# Mini_inverter_12v_to_220v.net
KiCad netlist of a schematic drawn in EasyEDA Pro
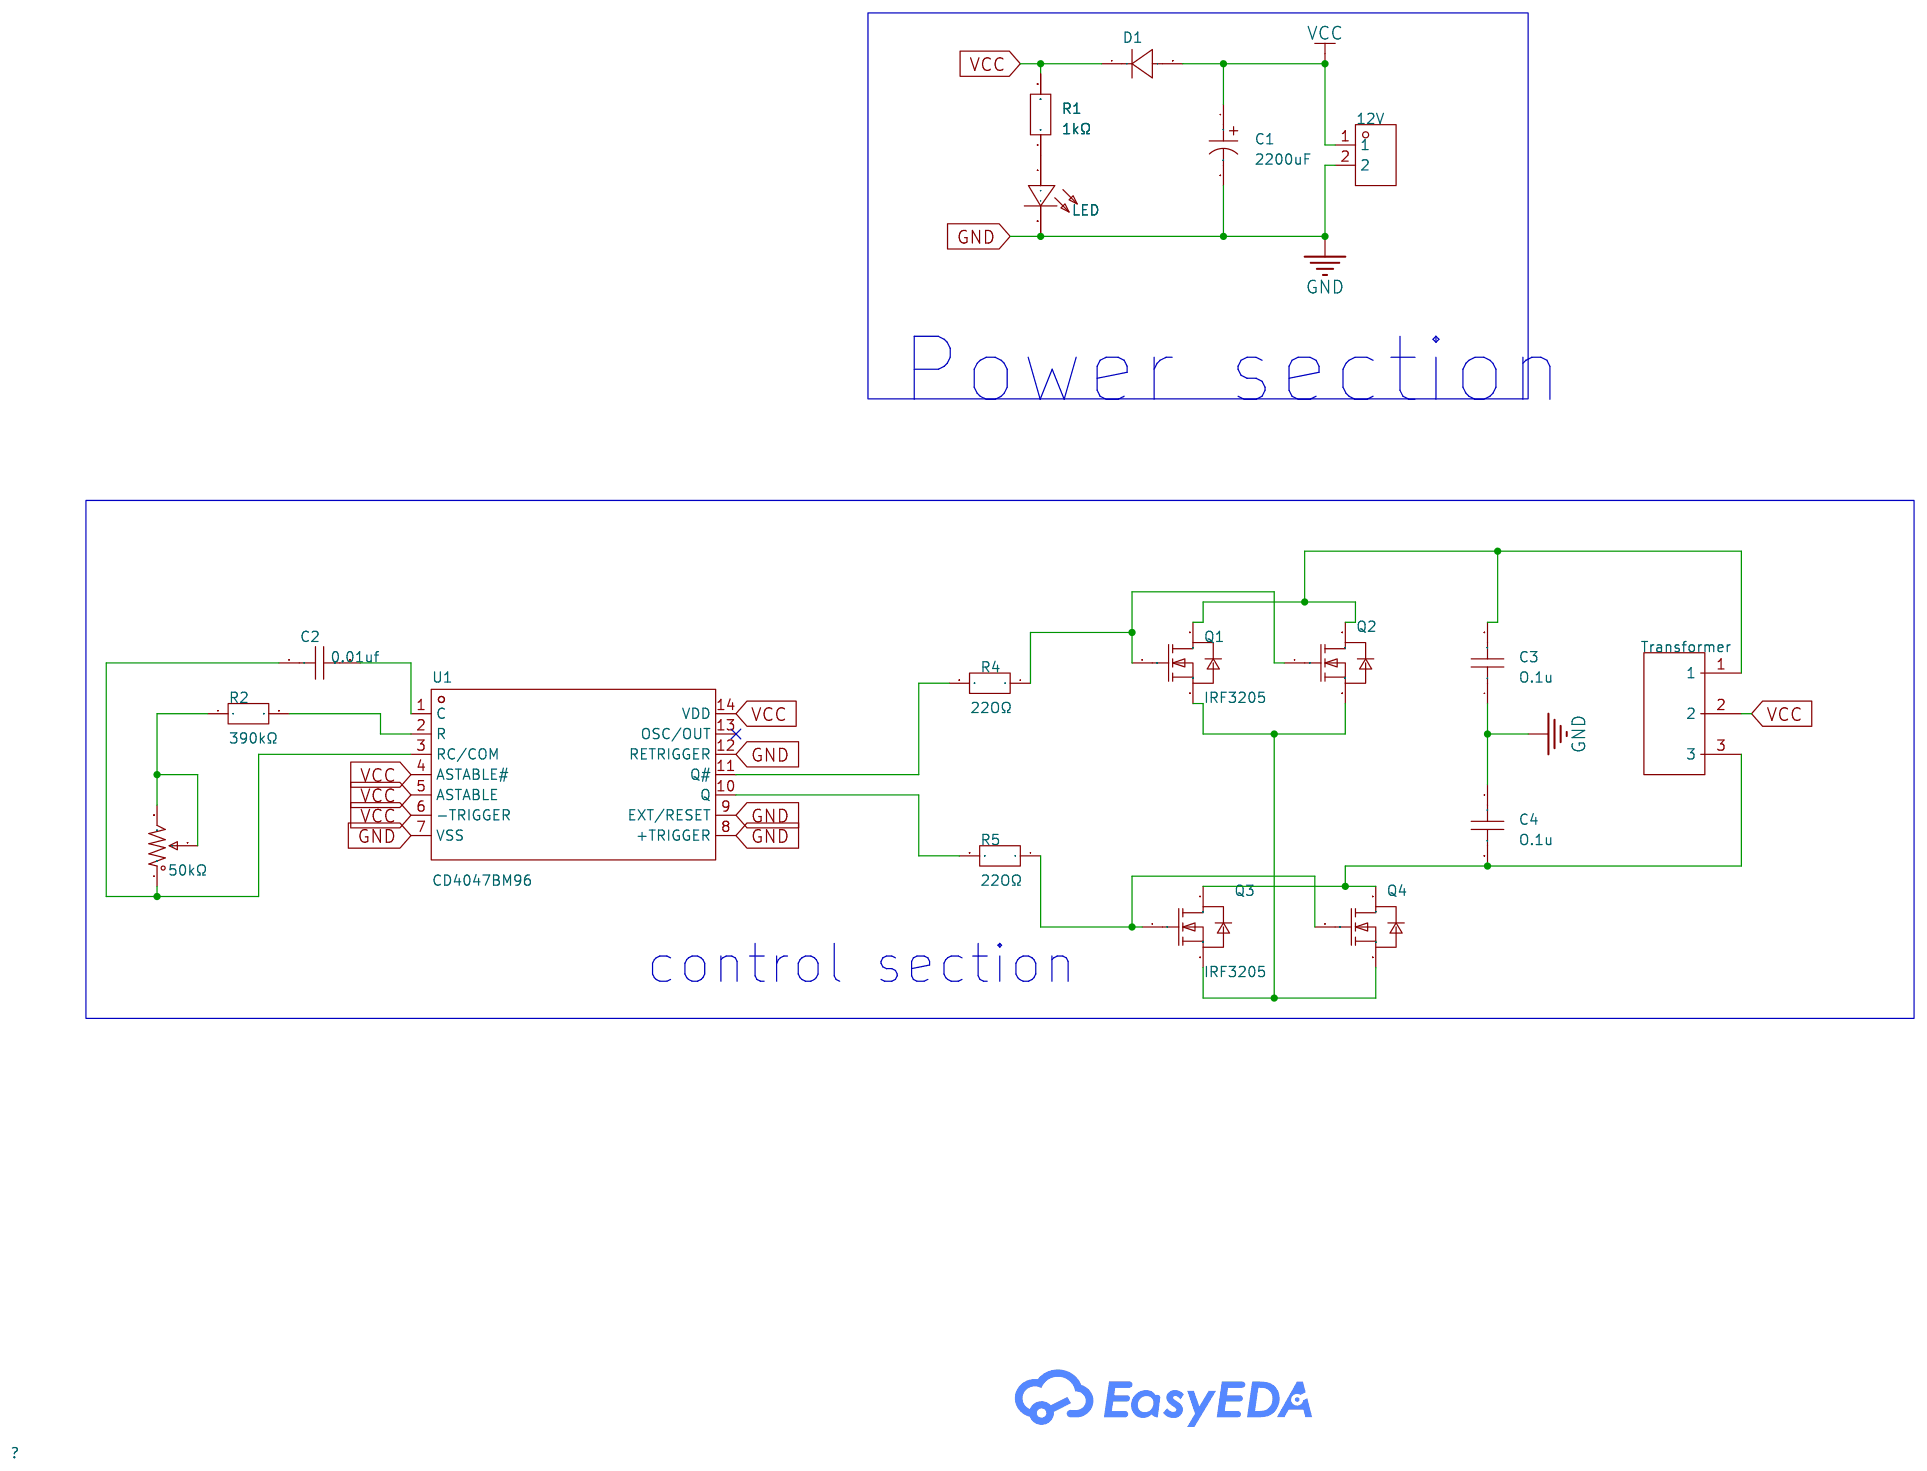
[diagram p0: schematic sheet]

(export (version "E")
  (design (tool "Eeschema 10.0.6"))
  (components
    (comp (ref "12V")
      (value "WJ126V-5.0-2P-16-00A")
      (footprint "easyedapro:CONN-TH_WJ126V-5.0-2P")
      (fields (field (name "Manufacturer") "KANGNEX(康奈克斯电气)"))
      (libsource (lib "easyedapro") (part "WJ126V-5.0-2P-16-00A"))
    )
    (comp (ref "C1")
      (value "2200uF")
      (footprint "easyedapro:CAP-TH_BD13.0-P5.00-D0.6-FD")
      (fields
        (field (name "Manufacturer Part") "ERA25V2200M13X21")
        (field (name "Manufacturer") "JIERR(捷而瑞)")
      )
      (libsource (lib "easyedapro") (part "ERA25V2200M13X21"))
    )
    (comp (ref "C2")
      (value "0.01uf")
      (footprint "easyedapro:C0603")
      (description "Capacitance:10nF Tolerance:±10% Tolerance:±10% Voltage Rating:50V Temperature Coefficient:X7R")
      (fields
        (field (name "Manufacturer Part") "FCC0603B103K500CT")
        (field (name "Manufacturer") "FOJAN(富捷)")
      )
      (libsource (lib "easyedapro") (part "FCC0603B103K500CT"))
    )
    (comp (ref "C3")
      (value "O.1u")
      (footprint "easyedapro:C0603")
      (description "Capacitance:10nF Tolerance:±10% Tolerance:±10% Voltage Rating:50V Temperature Coefficient:X7R")
      (fields
        (field (name "Manufacturer Part") "FCC0603B103K500CT")
        (field (name "Manufacturer") "FOJAN(富捷)")
      )
      (libsource (lib "easyedapro") (part "FCC0603B103K500CT"))
    )
    (comp (ref "C4")
      (value "O.1u")
      (footprint "easyedapro:C0603")
      (description "Capacitance:10nF Tolerance:±10% Tolerance:±10% Voltage Rating:50V Temperature Coefficient:X7R")
      (fields
        (field (name "Manufacturer Part") "FCC0603B103K500CT")
        (field (name "Manufacturer") "FOJAN(富捷)")
      )
      (libsource (lib "easyedapro") (part "FCC0603B103K500CT"))
    )
    (comp (ref "D1")
      (value "~")
      (footprint "easyedapro:DO-41_BD2.4-L4.7-P8.70-D0.9-RD")
      (libsource (lib "easyedapro") (part "D_1N4007"))
    )
    (comp (ref "Q1")
      (value "IRF3205")
      (footprint "easyedapro:TO-220-3_L10.0-W4.6-P2.54-L")
      (fields (field (name "Manufacturer") "minos(迈诺斯)"))
      (libsource (lib "easyedapro") (part "IRF3205"))
    )
    (comp (ref "Q2")
      (value "IRF3205")
      (footprint "easyedapro:TO-220-3_L10.0-W4.6-P2.54-L")
      (fields (field (name "Manufacturer") "minos(迈诺斯)"))
      (libsource (lib "easyedapro") (part "IRF3205"))
    )
    (comp (ref "Q3")
      (value "IRF3205")
      (footprint "easyedapro:TO-220-3_L10.0-W4.6-P2.54-L")
      (fields (field (name "Manufacturer") "minos(迈诺斯)"))
      (libsource (lib "easyedapro") (part "IRF3205"))
    )
    (comp (ref "Q4")
      (value "IRF3205")
      (footprint "easyedapro:TO-220-3_L10.0-W4.6-P2.54-L")
      (fields (field (name "Manufacturer") "minos(迈诺斯)"))
      (libsource (lib "easyedapro") (part "IRF3205"))
    )
    (comp (ref "R1")
      (value "1kΩ")
      (footprint "easyedapro:RES-TH_BD6.0-L17.5-P21.50-D0.8")
      (fields
        (field (name "Manufacturer Part") "RSMF5JB1K00")
        (field (name "Manufacturer") "SEI(Stackpole Electronics Inc.)")
      )
      (libsource (lib "easyedapro") (part "RSMF5JB1K00"))
    )
    (comp (ref "R2")
      (value "390kΩ")
      (footprint "easyedapro:RES-TH_BD6.0-L17.5-P21.50-D0.8")
      (fields
        (field (name "Manufacturer Part") "RSMF5JB1K00")
        (field (name "Manufacturer") "SEI(Stackpole Electronics Inc.)")
      )
      (libsource (lib "easyedapro") (part "RSMF5JB1K00"))
    )
    (comp (ref "R3")
      (value "50kΩ")
      (footprint "easyedapro:RES-ADJ-SMD_3P-L5.0-W4.5-P2.30-LS6.5_23BXX")
      (fields (field (name "Manufacturer Part") "23BR50KLFTR") (field (name "Manufacturer") "TT Electronics"))
      (libsource (lib "easyedapro") (part "23BR50KLFTR"))
    )
    (comp (ref "R4")
      (value "22OΩ")
      (footprint "easyedapro:RES-TH_BD6.0-L17.5-P21.50-D0.8")
      (fields
        (field (name "Manufacturer Part") "RSMF5JB1K00")
        (field (name "Manufacturer") "SEI(Stackpole Electronics Inc.)")
      )
      (libsource (lib "easyedapro") (part "RSMF5JB1K00"))
    )
    (comp (ref "R5")
      (value "22OΩ")
      (footprint "easyedapro:RES-TH_BD6.0-L17.5-P21.50-D0.8")
      (fields
        (field (name "Manufacturer Part") "RSMF5JB1K00")
        (field (name "Manufacturer") "SEI(Stackpole Electronics Inc.)")
      )
      (libsource (lib "easyedapro") (part "RSMF5JB1K00"))
    )
    (comp (ref "Transformer")
      (value "WJ126V-5.0-03P-14-00A")
      (footprint "easyedapro:CONN-TH_3P-P5.00_WJ126V-5.0-3P")
      (fields (field (name "Manufacturer") "KANGNEX(康奈克斯电气)"))
      (libsource (lib "easyedapro") (part "WJ126V-5.0-3P"))
    )
    (comp (ref "U1")
      (value "CD4047BM96")
      (footprint "easyedapro:SOP-14_L8.6-W3.9-P1.27-LS6.0-BL")
      (fields (field (name "Manufacturer") "TI(德州仪器)"))
      (libsource (lib "easyedapro") (part "CD4047BM96"))
    )
    (comp (ref "U2")
      (value "LED")
      (footprint "easyedapro:LED-TH_BD4.0-P2.54-FD_RED")
      (libsource (lib "easyedapro") (part "LED_C9900015665"))
    )
  )
  (nets
    (net (code "1") (name "GND") (class "Default")
      (node (ref "12V") (pin "2") (pinfunction "2_2") (pintype "unspecified"))
      (node (ref "C1") (pin "2") (pinfunction "2_2") (pintype "input"))
      (node (ref "C3") (pin "1") (pinfunction "1_1") (pintype "unspecified"))
      (node (ref "C4") (pin "1") (pinfunction "1_1") (pintype "unspecified"))
      (node (ref "U1") (pin "12") (pinfunction "RETRIGGER_12") (pintype "unspecified"))
      (node (ref "U1") (pin "7") (pinfunction "VSS_7") (pintype "unspecified"))
      (node (ref "U1") (pin "8") (pinfunction "+TRIGGER_8") (pintype "unspecified"))
      (node (ref "U1") (pin "9") (pinfunction "EXT/RESET_9") (pintype "unspecified"))
      (node (ref "U2") (pin "2") (pinfunction "-_2") (pintype "unspecified"))
    )
    (net (code "2") (name "Net-(Q1-D)") (class "Default")
      (node (ref "C3") (pin "2") (pinfunction "2_2") (pintype "unspecified"))
      (node (ref "Q1") (pin "2") (pinfunction "D_2") (pintype "unspecified"))
      (node (ref "Q2") (pin "2") (pinfunction "D_2") (pintype "unspecified"))
      (node (ref "Transformer") (pin "1") (pinfunction "1_1") (pintype "input"))
    )
    (net (code "3") (name "Net-(Q1-G)") (class "Default")
      (node (ref "Q1") (pin "1") (pinfunction "G_1") (pintype "unspecified"))
      (node (ref "Q2") (pin "1") (pinfunction "G_1") (pintype "unspecified"))
      (node (ref "R4") (pin "1") (pinfunction "1_1") (pintype "unspecified"))
    )
    (net (code "4") (name "Net-(Q1-S)") (class "Default")
      (node (ref "Q1") (pin "3") (pinfunction "S_3") (pintype "unspecified"))
      (node (ref "Q2") (pin "3") (pinfunction "S_3") (pintype "unspecified"))
      (node (ref "Q3") (pin "3") (pinfunction "S_3") (pintype "unspecified"))
      (node (ref "Q4") (pin "3") (pinfunction "S_3") (pintype "unspecified"))
    )
    (net (code "5") (name "Net-(Q3-D)") (class "Default")
      (node (ref "C4") (pin "2") (pinfunction "2_2") (pintype "unspecified"))
      (node (ref "Q3") (pin "2") (pinfunction "D_2") (pintype "unspecified"))
      (node (ref "Q4") (pin "2") (pinfunction "D_2") (pintype "unspecified"))
      (node (ref "Transformer") (pin "3") (pinfunction "3_3") (pintype "input"))
    )
    (net (code "6") (name "Net-(Q3-G)") (class "Default")
      (node (ref "Q3") (pin "1") (pinfunction "G_1") (pintype "unspecified"))
      (node (ref "Q4") (pin "1") (pinfunction "G_1") (pintype "unspecified"))
      (node (ref "R5") (pin "1") (pinfunction "1_1") (pintype "unspecified"))
    )
    (net (code "7") (name "Net-(R2-Pad1)") (class "Default")
      (node (ref "R2") (pin "1") (pinfunction "1_1") (pintype "unspecified"))
      (node (ref "R3") (pin "2") (pinfunction "2_2") (pintype "unspecified"))
      (node (ref "R3") (pin "3") (pinfunction "3_3") (pintype "unspecified"))
    )
    (net (code "8") (name "Net-(U1-C)") (class "Default")
      (node (ref "C2") (pin "2") (pinfunction "2_2") (pintype "unspecified"))
      (node (ref "U1") (pin "1") (pinfunction "C_1") (pintype "unspecified"))
    )
    (net (code "9") (name "Net-(U1-Q#)") (class "Default")
      (node (ref "R4") (pin "2") (pinfunction "2_2") (pintype "unspecified"))
      (node (ref "U1") (pin "11") (pinfunction "Q#_11") (pintype "unspecified"))
    )
    (net (code "10") (name "Net-(U1-Q)") (class "Default")
      (node (ref "R5") (pin "2") (pinfunction "2_2") (pintype "unspecified"))
      (node (ref "U1") (pin "10") (pinfunction "Q_10") (pintype "unspecified"))
    )
    (net (code "11") (name "Net-(U1-R)") (class "Default")
      (node (ref "R2") (pin "2") (pinfunction "2_2") (pintype "unspecified"))
      (node (ref "U1") (pin "2") (pinfunction "R_2") (pintype "unspecified"))
    )
    (net (code "12") (name "Net-(U1-RC{slash}COM)") (class "Default")
      (node (ref "C2") (pin "1") (pinfunction "1_1") (pintype "unspecified"))
      (node (ref "R3") (pin "1") (pinfunction "1_1") (pintype "unspecified"))
      (node (ref "U1") (pin "3") (pinfunction "RC/COM_3") (pintype "unspecified"))
    )
    (net (code "13") (name "Net-(U2-+)") (class "Default")
      (node (ref "R1") (pin "1") (pinfunction "1_1") (pintype "unspecified"))
      (node (ref "U2") (pin "1") (pinfunction "+_1") (pintype "unspecified"))
    )
    (net (code "14") (name "VCC") (class "Default")
      (node (ref "12V") (pin "1") (pinfunction "1_1") (pintype "unspecified"))
      (node (ref "C1") (pin "1") (pinfunction "1_1") (pintype "input"))
      (node (ref "D1") (pin "1") (pinfunction "K_1") (pintype "input"))
      (node (ref "D1") (pin "2") (pinfunction "A_2") (pintype "input"))
      (node (ref "R1") (pin "2") (pinfunction "2_2") (pintype "unspecified"))
      (node (ref "Transformer") (pin "2") (pinfunction "2_2") (pintype "input"))
      (node (ref "U1") (pin "14") (pinfunction "VDD_14") (pintype "unspecified"))
      (node (ref "U1") (pin "4") (pinfunction "ASTABLE#_4") (pintype "unspecified"))
      (node (ref "U1") (pin "5") (pinfunction "ASTABLE_5") (pintype "unspecified"))
      (node (ref "U1") (pin "6") (pinfunction "-TRIGGER_6") (pintype "unspecified"))
    )
    (net (code "15") (name "unconnected-(U1-OSC{slash}OUT-Pad13)") (class "Default")
      (node (ref "U1") (pin "13") (pinfunction "OSC/OUT_13") (pintype "unspecified+no_connect"))
    )
  )
)
